# WM.net
KiCad netlist of a schematic drawn in EAGLE
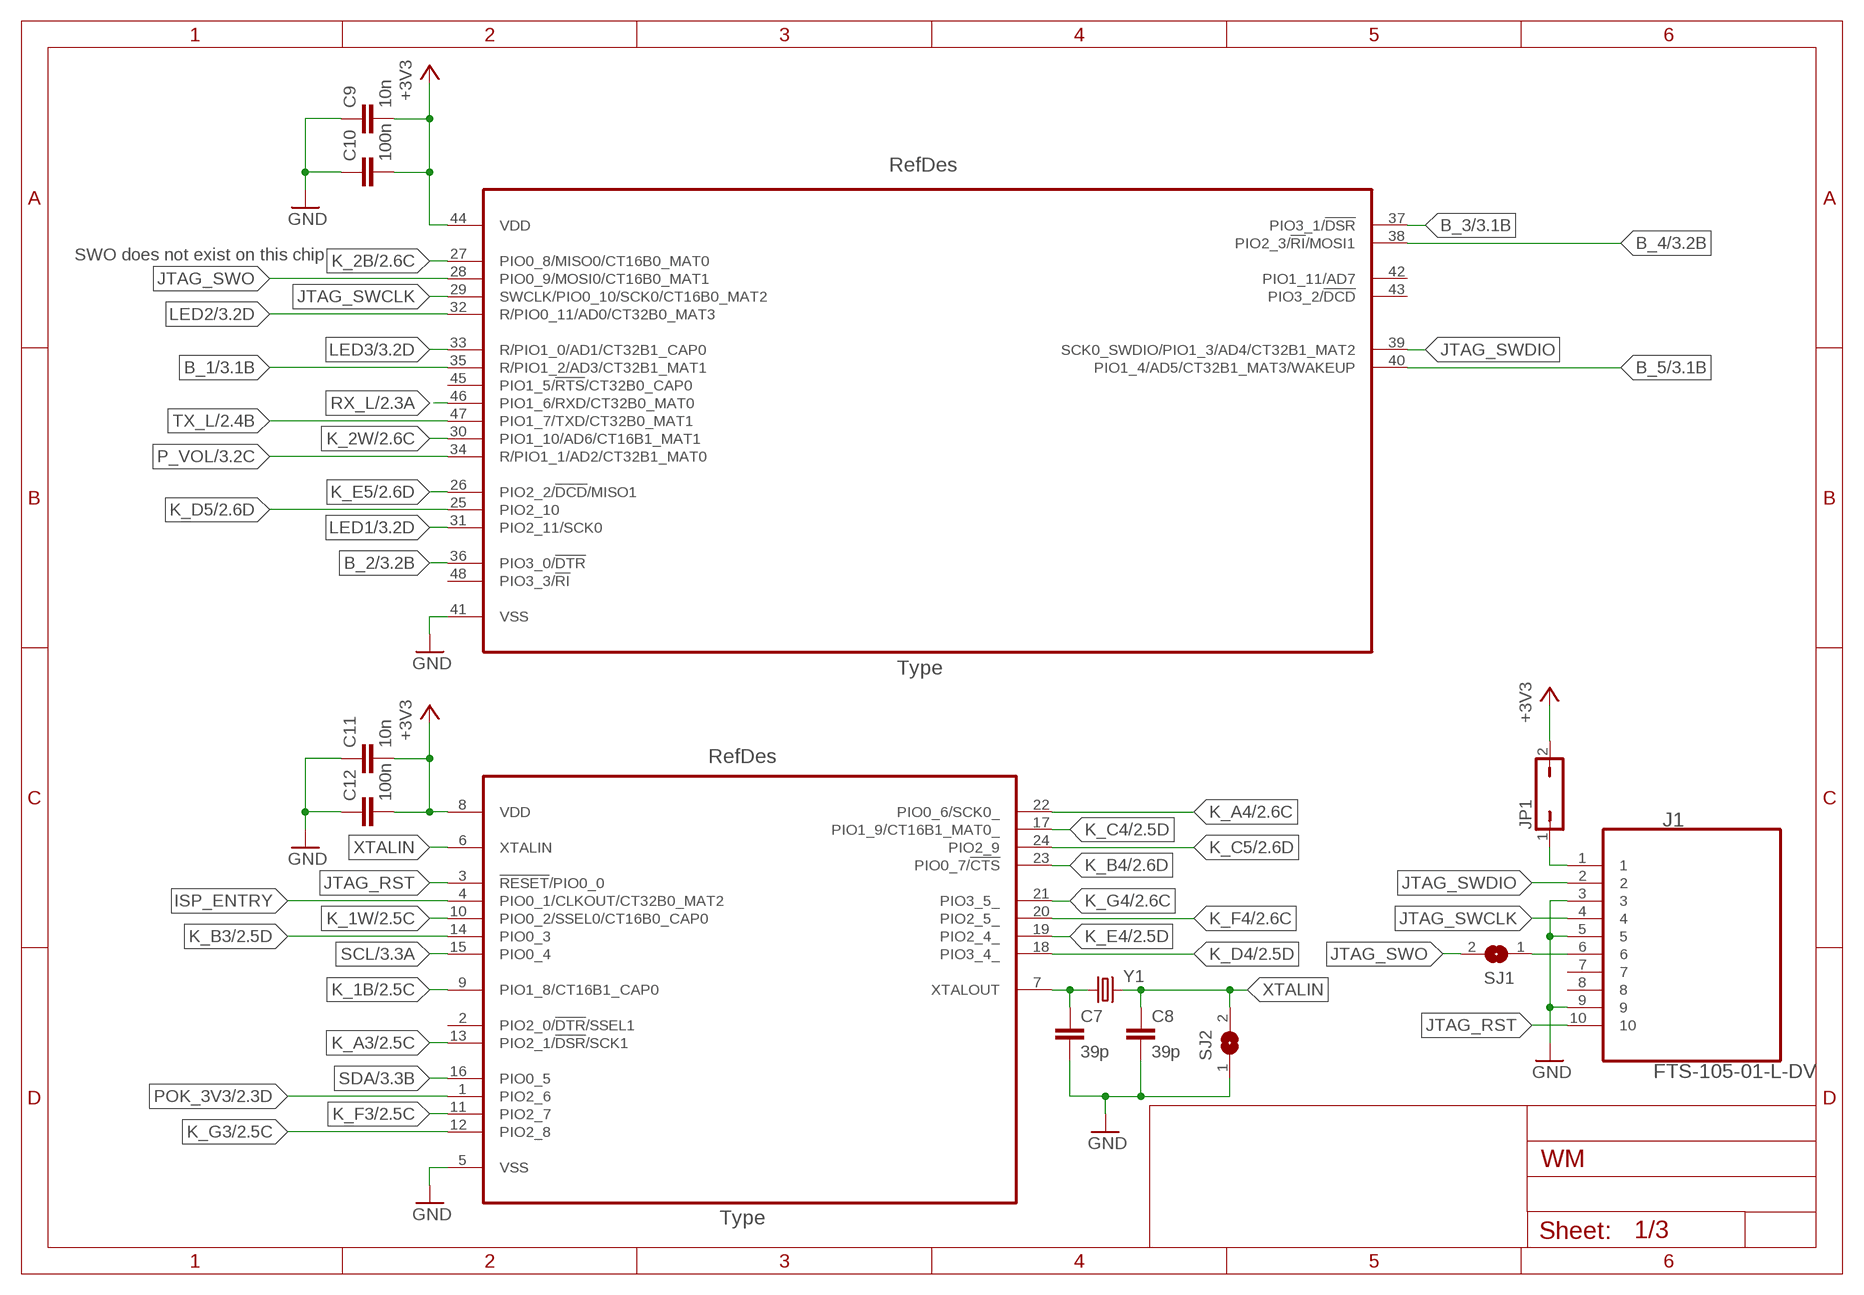
[diagram p0: schematic, sheet 1]
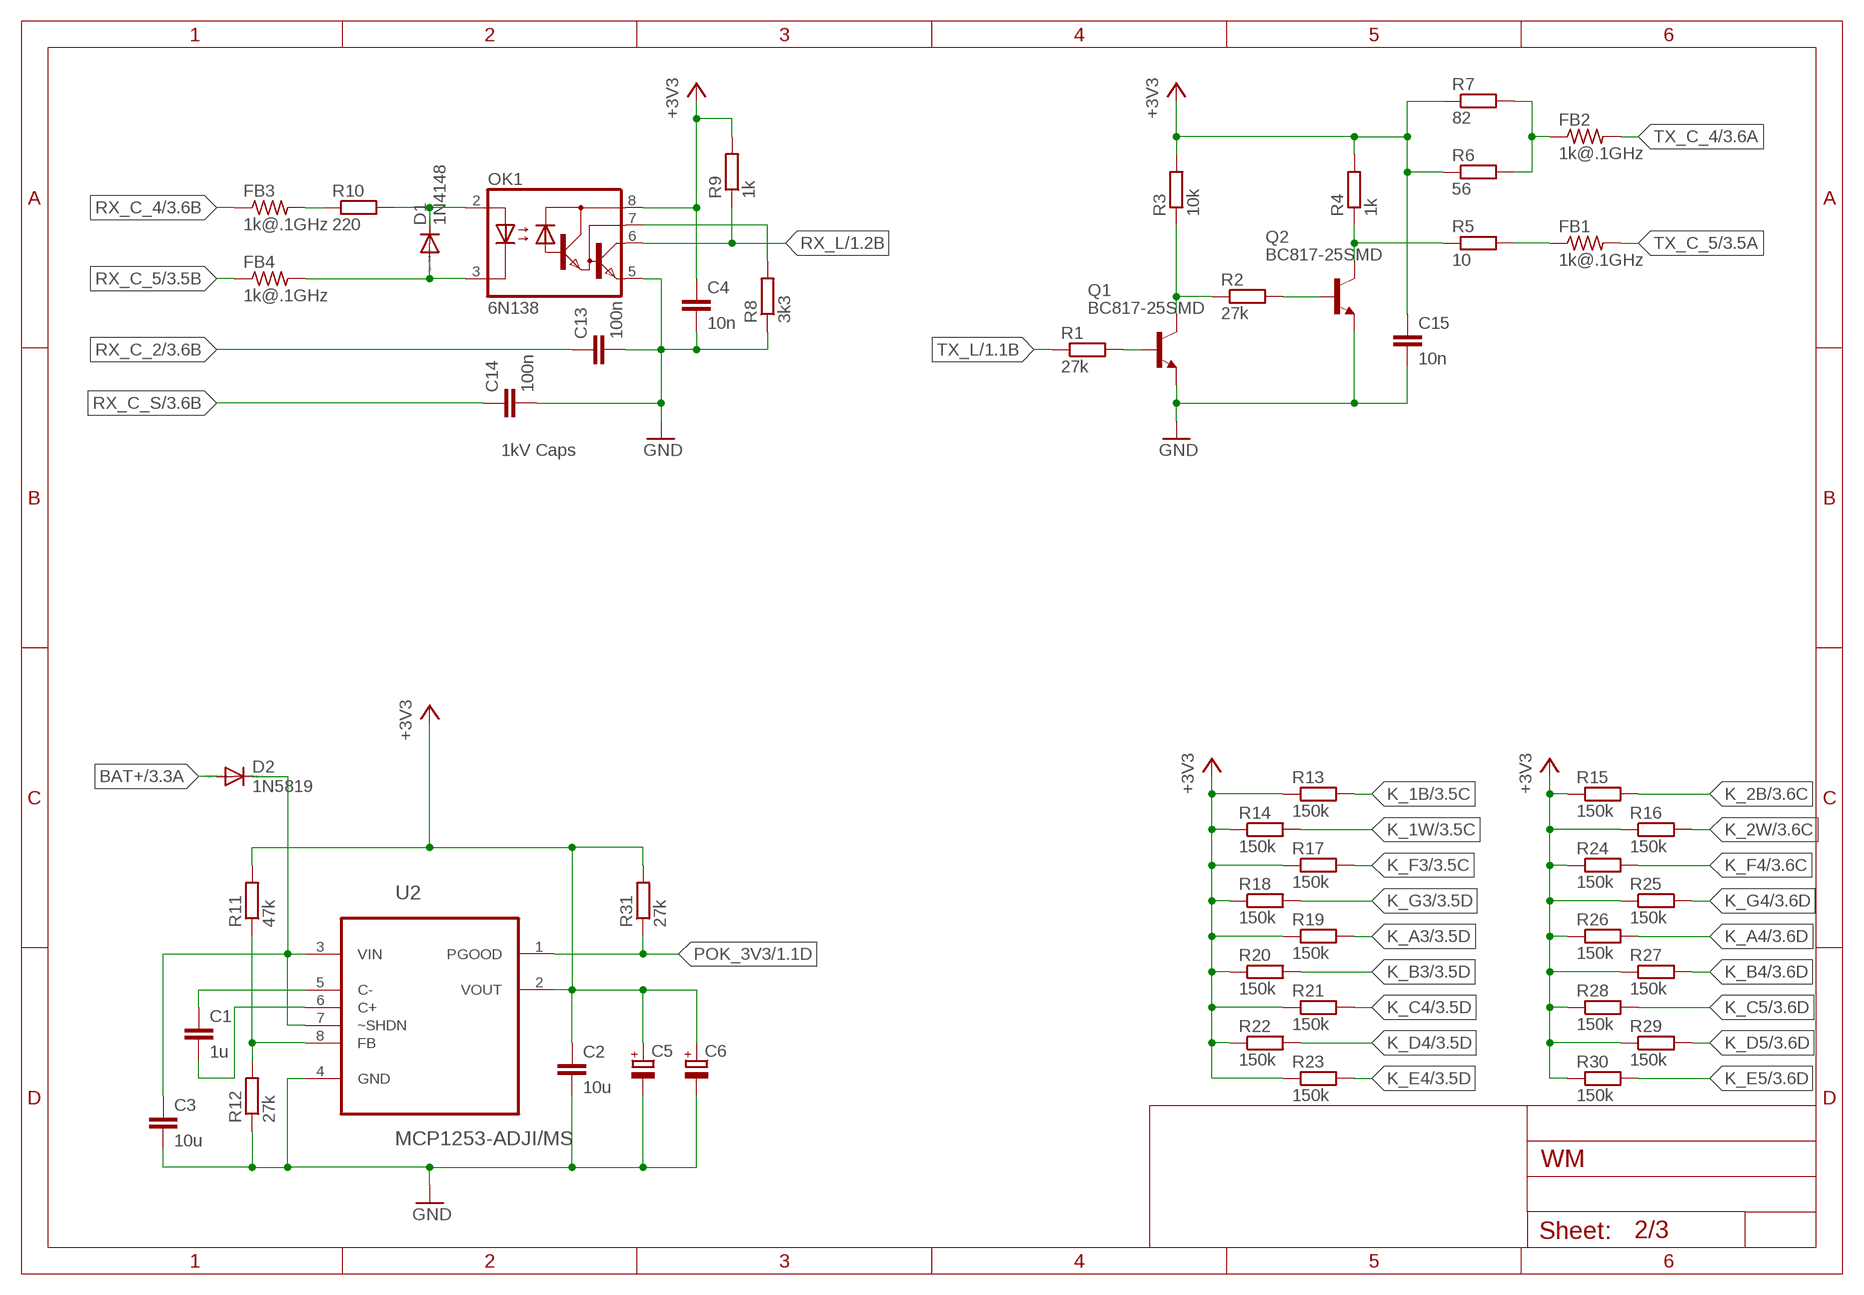
[diagram p1: schematic, sheet 2]
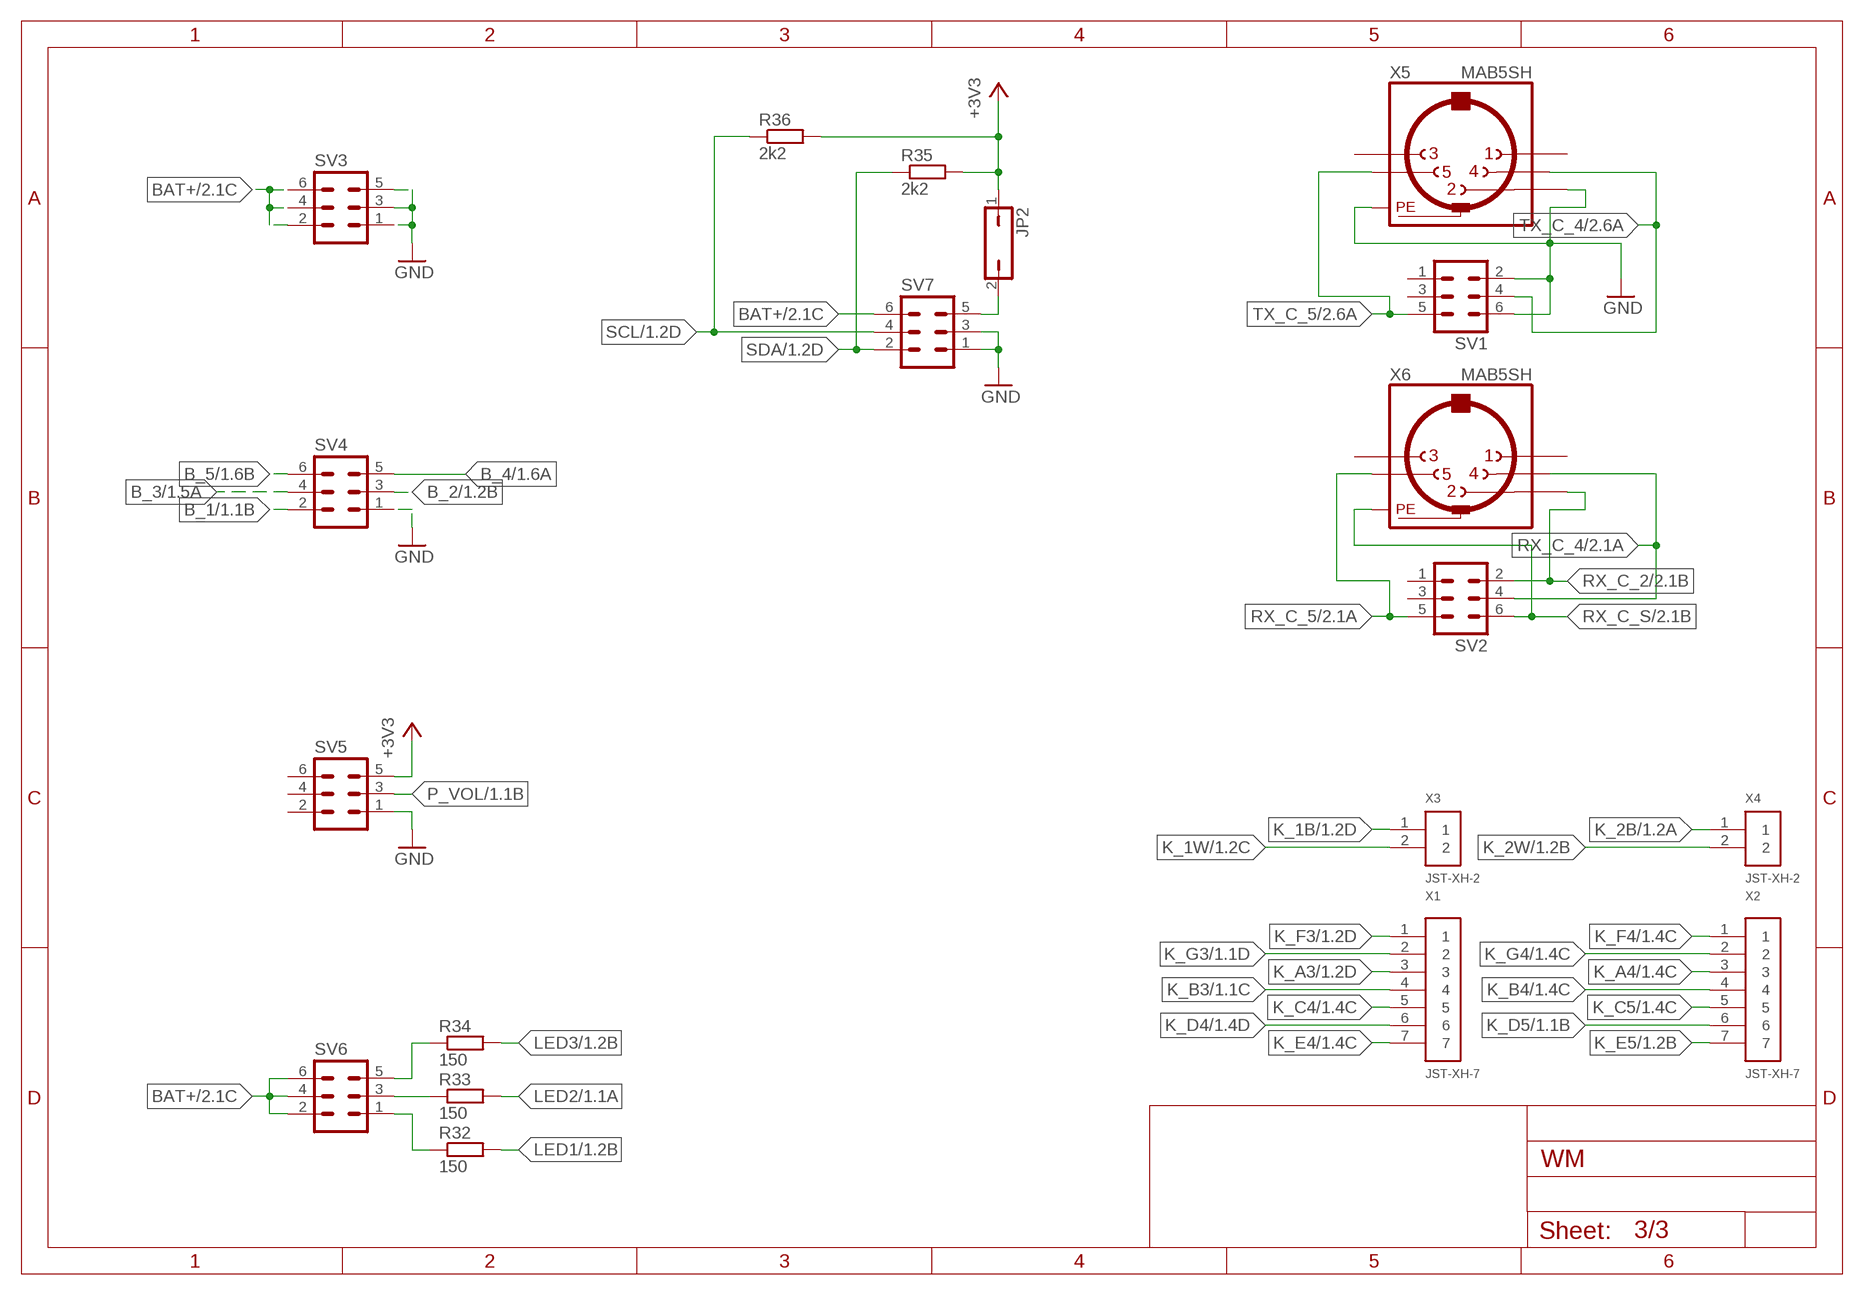
[diagram p2: schematic, sheet 3]

(export (version "E")
  (design (tool "Eeschema 10.0.6"))
  (components
    (comp (ref "C1")
      (value "1u")
      (footprint "eagle-import:C0805")
      (libsource (lib "eagle-import") (part "resistor_C-EUC0805"))
    )
    (comp (ref "C2")
      (value "10u")
      (footprint "eagle-import:C0805")
      (libsource (lib "eagle-import") (part "resistor_C-EUC0805"))
    )
    (comp (ref "C3")
      (value "10u")
      (footprint "eagle-import:C0805")
      (libsource (lib "eagle-import") (part "resistor_C-EUC0805"))
    )
    (comp (ref "C4")
      (value "10n")
      (footprint "eagle-import:C0805")
      (libsource (lib "eagle-import") (part "resistor_C-EUC0805"))
    )
    (comp (ref "C5")
      (value "CPOL-EUE2.5-6")
      (footprint "eagle-import:E2,5-6")
      (libsource (lib "eagle-import") (part "CPOL-EUE2.5-6"))
    )
    (comp (ref "C6")
      (value "CPOL-EUE2.5-6")
      (footprint "eagle-import:E2,5-6")
      (libsource (lib "eagle-import") (part "CPOL-EUE2.5-6"))
    )
    (comp (ref "C13")
      (value "100n")
      (footprint "eagle-import:C1210K")
      (libsource (lib "eagle-import") (part "resistor_C-EUC1210K"))
    )
    (comp (ref "C14")
      (value "100n")
      (footprint "eagle-import:C1210K")
      (libsource (lib "eagle-import") (part "resistor_C-EUC1210K"))
    )
    (comp (ref "C15")
      (value "10n")
      (footprint "eagle-import:C0805")
      (libsource (lib "eagle-import") (part "resistor_C-EUC0805"))
    )
    (comp (ref "D1")
      (value "1N4148")
      (footprint "eagle-import:SOD323-R")
      (libsource (lib "eagle-import") (part "DIODE-SOD323-R"))
    )
    (comp (ref "D2")
      (value "1N5819")
      (footprint "eagle-import:SOD123")
      (libsource (lib "eagle-import") (part "DIODE-SOD123"))
    )
    (comp (ref "FB1")
      (value "1k@.1GHz")
      (footprint "eagle-import:R0805")
      (libsource (lib "eagle-import") (part "R-US_R0805"))
    )
    (comp (ref "FB2")
      (value "1k@.1GHz")
      (footprint "eagle-import:R0805")
      (libsource (lib "eagle-import") (part "R-US_R0805"))
    )
    (comp (ref "FB3")
      (value "1k@.1GHz")
      (footprint "eagle-import:R0805")
      (libsource (lib "eagle-import") (part "R-US_R0805"))
    )
    (comp (ref "FB4")
      (value "1k@.1GHz")
      (footprint "eagle-import:R0805")
      (libsource (lib "eagle-import") (part "R-US_R0805"))
    )
    (comp (ref "OK1")
      (value "6N138")
      (footprint "eagle-import:DIL08")
      (fields (field (name "MF") "VISHAY/TELEFUNKEN"))
      (libsource (lib "eagle-import") (part "6N138"))
    )
    (comp (ref "Q1")
      (value "BC817-25SMD")
      (footprint "eagle-import:SOT23-BEC")
      (libsource (lib "eagle-import") (part "BC817SMD-25"))
    )
    (comp (ref "Q2")
      (value "BC817-25SMD")
      (footprint "eagle-import:SOT23-BEC")
      (libsource (lib "eagle-import") (part "BC817SMD-25"))
    )
    (comp (ref "R1")
      (value "27k")
      (footprint "eagle-import:R0805")
      (libsource (lib "eagle-import") (part "resistor_R-EU_R0805"))
    )
    (comp (ref "R2")
      (value "27k")
      (footprint "eagle-import:R0805")
      (libsource (lib "eagle-import") (part "resistor_R-EU_R0805"))
    )
    (comp (ref "R3")
      (value "10k")
      (footprint "eagle-import:R0805")
      (libsource (lib "eagle-import") (part "resistor_R-EU_R0805"))
    )
    (comp (ref "R4")
      (value "1k")
      (footprint "eagle-import:R0805")
      (libsource (lib "eagle-import") (part "resistor_R-EU_R0805"))
    )
    (comp (ref "R5")
      (value "10")
      (footprint "eagle-import:R0805")
      (libsource (lib "eagle-import") (part "resistor_R-EU_R0805"))
    )
    (comp (ref "R6")
      (value "56")
      (footprint "eagle-import:R0805")
      (libsource (lib "eagle-import") (part "resistor_R-EU_R0805"))
    )
    (comp (ref "R7")
      (value "82")
      (footprint "eagle-import:R0805")
      (libsource (lib "eagle-import") (part "resistor_R-EU_R0805"))
    )
    (comp (ref "R8")
      (value "3k3")
      (footprint "eagle-import:R0805")
      (libsource (lib "eagle-import") (part "resistor_R-EU_R0805"))
    )
    (comp (ref "R9")
      (value "1k")
      (footprint "eagle-import:R0805")
      (libsource (lib "eagle-import") (part "resistor_R-EU_R0805"))
    )
    (comp (ref "R10")
      (value "220")
      (footprint "eagle-import:R0805")
      (libsource (lib "eagle-import") (part "resistor_R-EU_R0805"))
    )
    (comp (ref "R11")
      (value "47k")
      (footprint "eagle-import:R0805")
      (libsource (lib "eagle-import") (part "R-EU_R0805"))
    )
    (comp (ref "R12")
      (value "27k")
      (footprint "eagle-import:R0805")
      (libsource (lib "eagle-import") (part "R-EU_R0805"))
    )
    (comp (ref "R13")
      (value "150k")
      (footprint "eagle-import:R0805")
      (libsource (lib "eagle-import") (part "R-EU_R0805"))
    )
    (comp (ref "R14")
      (value "150k")
      (footprint "eagle-import:R0805")
      (libsource (lib "eagle-import") (part "R-EU_R0805"))
    )
    (comp (ref "R15")
      (value "150k")
      (footprint "eagle-import:R0805")
      (libsource (lib "eagle-import") (part "R-EU_R0805"))
    )
    (comp (ref "R16")
      (value "150k")
      (footprint "eagle-import:R0805")
      (libsource (lib "eagle-import") (part "R-EU_R0805"))
    )
    (comp (ref "R17")
      (value "150k")
      (footprint "eagle-import:R0805")
      (libsource (lib "eagle-import") (part "R-EU_R0805"))
    )
    (comp (ref "R18")
      (value "150k")
      (footprint "eagle-import:R0805")
      (libsource (lib "eagle-import") (part "R-EU_R0805"))
    )
    (comp (ref "R19")
      (value "150k")
      (footprint "eagle-import:R0805")
      (libsource (lib "eagle-import") (part "R-EU_R0805"))
    )
    (comp (ref "R20")
      (value "150k")
      (footprint "eagle-import:R0805")
      (libsource (lib "eagle-import") (part "R-EU_R0805"))
    )
    (comp (ref "R21")
      (value "150k")
      (footprint "eagle-import:R0805")
      (libsource (lib "eagle-import") (part "R-EU_R0805"))
    )
    (comp (ref "R22")
      (value "150k")
      (footprint "eagle-import:R0805")
      (libsource (lib "eagle-import") (part "R-EU_R0805"))
    )
    (comp (ref "R23")
      (value "150k")
      (footprint "eagle-import:R0805")
      (libsource (lib "eagle-import") (part "R-EU_R0805"))
    )
    (comp (ref "R24")
      (value "150k")
      (footprint "eagle-import:R0805")
      (libsource (lib "eagle-import") (part "R-EU_R0805"))
    )
    (comp (ref "R25")
      (value "150k")
      (footprint "eagle-import:R0805")
      (libsource (lib "eagle-import") (part "R-EU_R0805"))
    )
    (comp (ref "R26")
      (value "150k")
      (footprint "eagle-import:R0805")
      (libsource (lib "eagle-import") (part "R-EU_R0805"))
    )
    (comp (ref "R27")
      (value "150k")
      (footprint "eagle-import:R0805")
      (libsource (lib "eagle-import") (part "R-EU_R0805"))
    )
    (comp (ref "R28")
      (value "150k")
      (footprint "eagle-import:R0805")
      (libsource (lib "eagle-import") (part "R-EU_R0805"))
    )
    (comp (ref "R29")
      (value "150k")
      (footprint "eagle-import:R0805")
      (libsource (lib "eagle-import") (part "R-EU_R0805"))
    )
    (comp (ref "R30")
      (value "150k")
      (footprint "eagle-import:R0805")
      (libsource (lib "eagle-import") (part "R-EU_R0805"))
    )
    (comp (ref "R31")
      (value "27k")
      (footprint "eagle-import:R0805")
      (libsource (lib "eagle-import") (part "resistor_R-EU_R0805"))
    )
    (comp (ref "U2")
      (value "MCP1253-ADJI/MS")
      (footprint "eagle-import:SOP65P490X118-8N")
      (libsource (lib "eagle-import") (part "MCP1253-ADJI/MS"))
    )
    (comp (ref "JP2")
      (value "JP1Q")
      (footprint "eagle-import:JP1")
      (libsource (lib "eagle-import") (part "JP1Q"))
    )
    (comp (ref "R32")
      (value "150")
      (footprint "eagle-import:R0805")
      (libsource (lib "eagle-import") (part "resistor_R-EU_R0805"))
    )
    (comp (ref "R33")
      (value "150")
      (footprint "eagle-import:R0805")
      (libsource (lib "eagle-import") (part "resistor_R-EU_R0805"))
    )
    (comp (ref "R34")
      (value "150")
      (footprint "eagle-import:R0805")
      (libsource (lib "eagle-import") (part "resistor_R-EU_R0805"))
    )
    (comp (ref "R35")
      (value "2k2")
      (footprint "eagle-import:R0805")
      (libsource (lib "eagle-import") (part "resistor_R-EU_R0805"))
    )
    (comp (ref "R36")
      (value "2k2")
      (footprint "eagle-import:R0805")
      (libsource (lib "eagle-import") (part "resistor_R-EU_R0805"))
    )
    (comp (ref "SV1")
      (value "ML6")
      (footprint "eagle-import:ML6")
      (libsource (lib "eagle-import") (part "ML6"))
    )
    (comp (ref "SV2")
      (value "ML6")
      (footprint "eagle-import:ML6")
      (libsource (lib "eagle-import") (part "ML6"))
    )
    (comp (ref "SV3")
      (value "ML6")
      (footprint "eagle-import:ML6")
      (libsource (lib "eagle-import") (part "ML6"))
    )
    (comp (ref "SV4")
      (value "ML6")
      (footprint "eagle-import:ML6")
      (libsource (lib "eagle-import") (part "ML6"))
    )
    (comp (ref "SV5")
      (value "ML6")
      (footprint "eagle-import:ML6")
      (libsource (lib "eagle-import") (part "ML6"))
    )
    (comp (ref "SV6")
      (value "ML6")
      (footprint "eagle-import:ML6")
      (libsource (lib "eagle-import") (part "ML6"))
    )
    (comp (ref "SV7")
      (value "ML6")
      (footprint "eagle-import:ML6")
      (libsource (lib "eagle-import") (part "ML6"))
    )
    (comp (ref "X1")
      (value "JST-XH-7")
      (footprint "eagle-import:JST-XH-7")
      (fields (field (name "MF") "MOLEX") (field (name "MPN") "22-23-2071"))
      (libsource (lib "eagle-import") (part "JST-XH-7"))
    )
    (comp (ref "X2")
      (value "JST-XH-7")
      (footprint "eagle-import:JST-XH-7")
      (fields (field (name "MF") "MOLEX") (field (name "MPN") "22-23-2071"))
      (libsource (lib "eagle-import") (part "JST-XH-7"))
    )
    (comp (ref "X3")
      (value "JST-XH-2")
      (footprint "eagle-import:JST-XH-2")
      (libsource (lib "eagle-import") (part "JST-XH-2"))
    )
    (comp (ref "X4")
      (value "JST-XH-2")
      (footprint "eagle-import:JST-XH-2")
      (libsource (lib "eagle-import") (part "JST-XH-2"))
    )
    (comp (ref "X5")
      (value "MAB5SH")
      (footprint "eagle-import:MAB5SH")
      (libsource (lib "eagle-import") (part "MAB5SH"))
    )
    (comp (ref "X6")
      (value "MAB5SH")
      (footprint "eagle-import:MAB5SH")
      (libsource (lib "eagle-import") (part "MAB5SH"))
    )
    (comp (ref "C7")
      (value "39p")
      (footprint "eagle-import:C0805")
      (libsource (lib "eagle-import") (part "resistor_C-EUC0805"))
    )
    (comp (ref "C8")
      (value "39p")
      (footprint "eagle-import:C0805")
      (libsource (lib "eagle-import") (part "resistor_C-EUC0805"))
    )
    (comp (ref "C9")
      (value "10n")
      (footprint "eagle-import:C0805")
      (libsource (lib "eagle-import") (part "C-EUC0805"))
    )
    (comp (ref "C10")
      (value "100n")
      (footprint "eagle-import:C0805")
      (libsource (lib "eagle-import") (part "C-EUC0805"))
    )
    (comp (ref "C11")
      (value "10n")
      (footprint "eagle-import:C0805")
      (libsource (lib "eagle-import") (part "C-EUC0805"))
    )
    (comp (ref "C12")
      (value "100n")
      (footprint "eagle-import:C0805")
      (libsource (lib "eagle-import") (part "C-EUC0805"))
    )
    (comp (ref "J1")
      (value "FTS-105-01-L-DV")
      (footprint "eagle-import:SAMTEC_FTS-105-01-L-DV")
      (libsource (lib "eagle-import") (part "FTS-105-01-L-DV"))
    )
    (comp (ref "JP1")
      (value "JP1Q")
      (footprint "eagle-import:JP1")
      (libsource (lib "eagle-import") (part "JP1Q"))
    )
    (comp (ref "SJ1") (value "SJ") (footprint "eagle-import:SJ") (libsource (lib "eagle-import") (part "SJ")))
    (comp (ref "SJ2") (value "SJ") (footprint "eagle-import:SJ") (libsource (lib "eagle-import") (part "SJ")))
    (comp (ref "U1")
      (value "LPC1113FBD48/302,1")
      (footprint "eagle-import:QFP50P900X900X160-48N")
      (libsource (lib "eagle-import") (part "LPC1113FBD48/302,1"))
    )
    (comp (ref "Y1")
      (value "CRYSTALHC49UP")
      (footprint "eagle-import:HC49UP")
      (libsource (lib "eagle-import") (part "CRYSTALHC49UP"))
    )
  )
  (nets
    (net (code "1") (name "+3V3") (class "Default")
      (node (ref "C10") (pin "2") (pinfunction "2_2") (pintype "passive"))
      (node (ref "C11") (pin "2") (pinfunction "2_2") (pintype "passive"))
      (node (ref "C12") (pin "2") (pinfunction "2_2") (pintype "passive"))
      (node (ref "C15") (pin "1") (pinfunction "1_1") (pintype "passive"))
      (node (ref "C2") (pin "1") (pinfunction "1_1") (pintype "passive"))
      (node (ref "C4") (pin "1") (pinfunction "1_1") (pintype "passive"))
      (node (ref "C5") (pin "+") (pinfunction "+_+") (pintype "passive"))
      (node (ref "C6") (pin "+") (pinfunction "+_+") (pintype "passive"))
      (node (ref "C9") (pin "2") (pinfunction "2_2") (pintype "passive"))
      (node (ref "JP1") (pin "2") (pinfunction "2_2") (pintype "passive"))
      (node (ref "JP2") (pin "1") (pinfunction "1_1") (pintype "passive"))
      (node (ref "OK1") (pin "8") (pinfunction "VCC_8") (pintype "passive"))
      (node (ref "R11") (pin "2") (pinfunction "2_2") (pintype "passive"))
      (node (ref "R13") (pin "1") (pinfunction "1_1") (pintype "passive"))
      (node (ref "R14") (pin "1") (pinfunction "1_1") (pintype "passive"))
      (node (ref "R15") (pin "1") (pinfunction "1_1") (pintype "passive"))
      (node (ref "R16") (pin "1") (pinfunction "1_1") (pintype "passive"))
      (node (ref "R17") (pin "1") (pinfunction "1_1") (pintype "passive"))
      (node (ref "R18") (pin "1") (pinfunction "1_1") (pintype "passive"))
      (node (ref "R19") (pin "1") (pinfunction "1_1") (pintype "passive"))
      (node (ref "R20") (pin "1") (pinfunction "1_1") (pintype "passive"))
      (node (ref "R21") (pin "1") (pinfunction "1_1") (pintype "passive"))
      (node (ref "R22") (pin "1") (pinfunction "1_1") (pintype "passive"))
      (node (ref "R23") (pin "1") (pinfunction "1_1") (pintype "passive"))
      (node (ref "R24") (pin "1") (pinfunction "1_1") (pintype "passive"))
      (node (ref "R25") (pin "1") (pinfunction "1_1") (pintype "passive"))
      (node (ref "R26") (pin "1") (pinfunction "1_1") (pintype "passive"))
      (node (ref "R27") (pin "1") (pinfunction "1_1") (pintype "passive"))
      (node (ref "R28") (pin "1") (pinfunction "1_1") (pintype "passive"))
      (node (ref "R29") (pin "1") (pinfunction "1_1") (pintype "passive"))
      (node (ref "R3") (pin "2") (pinfunction "2_2") (pintype "passive"))
      (node (ref "R30") (pin "1") (pinfunction "1_1") (pintype "passive"))
      (node (ref "R31") (pin "2") (pinfunction "2_2") (pintype "passive"))
      (node (ref "R35") (pin "2") (pinfunction "2_2") (pintype "passive"))
      (node (ref "R36") (pin "2") (pinfunction "2_2") (pintype "passive"))
      (node (ref "R4") (pin "2") (pinfunction "2_2") (pintype "passive"))
      (node (ref "R6") (pin "1") (pinfunction "1_1") (pintype "passive"))
      (node (ref "R7") (pin "1") (pinfunction "1_1") (pintype "passive"))
      (node (ref "R9") (pin "2") (pinfunction "2_2") (pintype "passive"))
      (node (ref "SV5") (pin "5") (pinfunction "5_5") (pintype "passive"))
      (node (ref "U1") (pin "44") (pinfunction "VDD_44") (pintype "power_in"))
      (node (ref "U1") (pin "8") (pinfunction "VDD_8") (pintype "power_in"))
      (node (ref "U2") (pin "2") (pinfunction "VOUT_2") (pintype "output"))
    )
    (net (code "2") (name "BAT+") (class "Default")
      (node (ref "D2") (pin "A") (pinfunction "A_A") (pintype "passive"))
      (node (ref "SV3") (pin "2") (pinfunction "2_2") (pintype "passive"))
      (node (ref "SV3") (pin "4") (pinfunction "4_4") (pintype "passive"))
      (node (ref "SV3") (pin "6") (pinfunction "6_6") (pintype "passive"))
      (node (ref "SV6") (pin "2") (pinfunction "2_2") (pintype "passive"))
      (node (ref "SV6") (pin "4") (pinfunction "4_4") (pintype "passive"))
      (node (ref "SV6") (pin "6") (pinfunction "6_6") (pintype "passive"))
      (node (ref "SV7") (pin "6") (pinfunction "6_6") (pintype "passive"))
    )
    (net (code "3") (name "B_1") (class "Default")
      (node (ref "SV4") (pin "2") (pinfunction "2_2") (pintype "passive"))
      (node (ref "U1") (pin "35") (pinfunction "R/PIO1_2/AD3/CT32B1_MAT1_35") (pintype "bidirectional"))
    )
    (net (code "4") (name "B_2") (class "Default")
      (node (ref "SV4") (pin "3") (pinfunction "3_3") (pintype "passive"))
      (node (ref "U1") (pin "36") (pinfunction "PIO3_0/~{DTR}_36") (pintype "bidirectional"))
    )
    (net (code "5") (name "B_3") (class "Default")
      (node (ref "SV4") (pin "4") (pinfunction "4_4") (pintype "passive"))
      (node (ref "U1") (pin "37") (pinfunction "PIO3_1/~{DSR}_37") (pintype "bidirectional"))
    )
    (net (code "6") (name "B_4") (class "Default")
      (node (ref "SV4") (pin "5") (pinfunction "5_5") (pintype "passive"))
      (node (ref "U1") (pin "38") (pinfunction "PIO2_3/~{RI}/MOSI1_38") (pintype "bidirectional"))
    )
    (net (code "7") (name "B_5") (class "Default")
      (node (ref "SV4") (pin "6") (pinfunction "6_6") (pintype "passive"))
      (node (ref "U1") (pin "40") (pinfunction "PIO1_4/AD5/CT32B1_MAT3/WAKEUP_40") (pintype "bidirectional"))
    )
    (net (code "8") (name "GND") (class "Default")
      (node (ref "C10") (pin "1") (pinfunction "1_1") (pintype "passive"))
      (node (ref "C11") (pin "1") (pinfunction "1_1") (pintype "passive"))
      (node (ref "C12") (pin "1") (pinfunction "1_1") (pintype "passive"))
      (node (ref "C13") (pin "2") (pinfunction "2_2") (pintype "passive"))
      (node (ref "C14") (pin "2") (pinfunction "2_2") (pintype "passive"))
      (node (ref "C15") (pin "2") (pinfunction "2_2") (pintype "passive"))
      (node (ref "C2") (pin "2") (pinfunction "2_2") (pintype "passive"))
      (node (ref "C3") (pin "2") (pinfunction "2_2") (pintype "passive"))
      (node (ref "C4") (pin "2") (pinfunction "2_2") (pintype "passive"))
      (node (ref "C5") (pin "-") (pinfunction "-_-") (pintype "passive"))
      (node (ref "C6") (pin "-") (pinfunction "-_-") (pintype "passive"))
      (node (ref "C7") (pin "2") (pinfunction "2_2") (pintype "passive"))
      (node (ref "C8") (pin "2") (pinfunction "2_2") (pintype "passive"))
      (node (ref "C9") (pin "1") (pinfunction "1_1") (pintype "passive"))
      (node (ref "J1") (pin "3") (pinfunction "3_3") (pintype "passive"))
      (node (ref "J1") (pin "5") (pinfunction "5_5") (pintype "passive"))
      (node (ref "J1") (pin "9") (pinfunction "9_9") (pintype "passive"))
      (node (ref "OK1") (pin "5") (pinfunction "GND_5") (pintype "passive"))
      (node (ref "Q1") (pin "E") (pinfunction "E_E") (pintype "passive"))
      (node (ref "Q2") (pin "E") (pinfunction "E_E") (pintype "passive"))
      (node (ref "R12") (pin "1") (pinfunction "1_1") (pintype "passive"))
      (node (ref "R8") (pin "1") (pinfunction "1_1") (pintype "passive"))
      (node (ref "SJ2") (pin "1") (pinfunction "1_1") (pintype "passive"))
      (node (ref "SV1") (pin "2") (pinfunction "2_2") (pintype "passive"))
      (node (ref "SV1") (pin "6") (pinfunction "6_6") (pintype "passive"))
      (node (ref "SV3") (pin "1") (pinfunction "1_1") (pintype "passive"))
      (node (ref "SV3") (pin "3") (pinfunction "3_3") (pintype "passive"))
      (node (ref "SV3") (pin "5") (pinfunction "5_5") (pintype "passive"))
      (node (ref "SV4") (pin "1") (pinfunction "1_1") (pintype "passive"))
      (node (ref "SV5") (pin "1") (pinfunction "1_1") (pintype "passive"))
      (node (ref "SV7") (pin "1") (pinfunction "1_1") (pintype "passive"))
      (node (ref "SV7") (pin "3") (pinfunction "3_3") (pintype "passive"))
      (node (ref "U1") (pin "41") (pinfunction "VSS_41") (pintype "passive"))
      (node (ref "U1") (pin "5") (pinfunction "VSS_5") (pintype "passive"))
      (node (ref "U2") (pin "4") (pinfunction "GND_4") (pintype "passive"))
      (node (ref "X5") (pin "2") (pinfunction "2_2") (pintype "passive"))
      (node (ref "X5") (pin "PE") (pinfunction "PE_PE") (pintype "power_in"))
      (node (ref "X5") (pin "PE@") (pinfunction "PE_PE@") (pintype "power_in"))
    )
    (net (code "9") (name "ISP_ENTRY") (class "Default")
      (node (ref "U1") (pin "4") (pinfunction "PIO0_1/CLKOUT/CT32B0_MAT2_4") (pintype "bidirectional"))
    )
    (net (code "10") (name "JTAG_RST") (class "Default")
      (node (ref "J1") (pin "10") (pinfunction "10_10") (pintype "passive"))
      (node (ref "U1") (pin "3") (pinfunction "~{RESET}/PIO0_0_3") (pintype "input"))
    )
    (net (code "11") (name "JTAG_SWCLK") (class "Default")
      (node (ref "J1") (pin "4") (pinfunction "4_4") (pintype "passive"))
      (node (ref "U1") (pin "29") (pinfunction "SWCLK/PIO0_10/SCK0/CT16B0_MAT2_29") (pintype "bidirectional"))
    )
    (net (code "12") (name "JTAG_SWDIO") (class "Default")
      (node (ref "J1") (pin "2") (pinfunction "2_2") (pintype "passive"))
      (node (ref "U1") (pin "39") (pinfunction "SCK0_SWDIO/PIO1_3/AD4/CT32B1_MAT2_39") (pintype "bidirectional"))
    )
    (net (code "13") (name "JTAG_SWO") (class "Default")
      (node (ref "SJ1") (pin "2") (pinfunction "2_2") (pintype "passive"))
      (node (ref "U1") (pin "28") (pinfunction "PIO0_9/MOSI0/CT16B0_MAT1_28") (pintype "bidirectional"))
    )
    (net (code "14") (name "K_1B") (class "Default")
      (node (ref "R13") (pin "2") (pinfunction "2_2") (pintype "passive"))
      (node (ref "U1") (pin "9") (pinfunction "PIO1_8/CT16B1_CAP0_9") (pintype "bidirectional"))
      (node (ref "X3") (pin "1") (pinfunction "1_1") (pintype "bidirectional"))
    )
    (net (code "15") (name "K_1W") (class "Default")
      (node (ref "R14") (pin "2") (pinfunction "2_2") (pintype "passive"))
      (node (ref "U1") (pin "10") (pinfunction "PIO0_2/SSEL0/CT16B0_CAP0_10") (pintype "bidirectional"))
      (node (ref "X3") (pin "2") (pinfunction "2_2") (pintype "bidirectional"))
    )
    (net (code "16") (name "K_2B") (class "Default")
      (node (ref "R15") (pin "2") (pinfunction "2_2") (pintype "passive"))
      (node (ref "U1") (pin "27") (pinfunction "PIO0_8/MISO0/CT16B0_MAT0_27") (pintype "bidirectional"))
      (node (ref "X4") (pin "1") (pinfunction "1_1") (pintype "bidirectional"))
    )
    (net (code "17") (name "K_2W") (class "Default")
      (node (ref "R16") (pin "2") (pinfunction "2_2") (pintype "passive"))
      (node (ref "U1") (pin "30") (pinfunction "PIO1_10/AD6/CT16B1_MAT1_30") (pintype "bidirectional"))
      (node (ref "X4") (pin "2") (pinfunction "2_2") (pintype "bidirectional"))
    )
    (net (code "18") (name "K_A3") (class "Default")
      (node (ref "R19") (pin "2") (pinfunction "2_2") (pintype "passive"))
      (node (ref "U1") (pin "13") (pinfunction "PIO2_1/~{DSR}/SCK1_13") (pintype "bidirectional"))
      (node (ref "X1") (pin "3") (pinfunction "3_3") (pintype "bidirectional"))
    )
    (net (code "19") (name "K_A4") (class "Default")
      (node (ref "R26") (pin "2") (pinfunction "2_2") (pintype "passive"))
      (node (ref "U1") (pin "22") (pinfunction "PIO0_6/SCK0__22") (pintype "bidirectional"))
      (node (ref "X2") (pin "3") (pinfunction "3_3") (pintype "bidirectional"))
    )
    (net (code "20") (name "K_B3") (class "Default")
      (node (ref "R20") (pin "2") (pinfunction "2_2") (pintype "passive"))
      (node (ref "U1") (pin "14") (pinfunction "PIO0_3_14") (pintype "bidirectional"))
      (node (ref "X1") (pin "4") (pinfunction "4_4") (pintype "bidirectional"))
    )
    (net (code "21") (name "K_B4") (class "Default")
      (node (ref "R27") (pin "2") (pinfunction "2_2") (pintype "passive"))
      (node (ref "U1") (pin "23") (pinfunction "PIO0_7/~{CTS}_23") (pintype "bidirectional"))
      (node (ref "X2") (pin "4") (pinfunction "4_4") (pintype "bidirectional"))
    )
    (net (code "22") (name "K_C4") (class "Default")
      (node (ref "R21") (pin "2") (pinfunction "2_2") (pintype "passive"))
      (node (ref "U1") (pin "17") (pinfunction "PIO1_9/CT16B1_MAT0__17") (pintype "bidirectional"))
      (node (ref "X1") (pin "5") (pinfunction "5_5") (pintype "bidirectional"))
    )
    (net (code "23") (name "K_C5") (class "Default")
      (node (ref "R28") (pin "2") (pinfunction "2_2") (pintype "passive"))
      (node (ref "U1") (pin "24") (pinfunction "PIO2_9_24") (pintype "bidirectional"))
      (node (ref "X2") (pin "5") (pinfunction "5_5") (pintype "bidirectional"))
    )
    (net (code "24") (name "K_D4") (class "Default")
      (node (ref "R22") (pin "2") (pinfunction "2_2") (pintype "passive"))
      (node (ref "U1") (pin "18") (pinfunction "PIO3_4__18") (pintype "bidirectional"))
      (node (ref "X1") (pin "6") (pinfunction "6_6") (pintype "bidirectional"))
    )
    (net (code "25") (name "K_D5") (class "Default")
      (node (ref "R29") (pin "2") (pinfunction "2_2") (pintype "passive"))
      (node (ref "U1") (pin "25") (pinfunction "PIO2_10_25") (pintype "bidirectional"))
      (node (ref "X2") (pin "6") (pinfunction "6_6") (pintype "bidirectional"))
    )
    (net (code "26") (name "K_E4") (class "Default")
      (node (ref "R23") (pin "2") (pinfunction "2_2") (pintype "passive"))
      (node (ref "U1") (pin "19") (pinfunction "PIO2_4__19") (pintype "bidirectional"))
      (node (ref "X1") (pin "7") (pinfunction "7_7") (pintype "bidirectional"))
    )
    (net (code "27") (name "K_E5") (class "Default")
      (node (ref "R30") (pin "2") (pinfunction "2_2") (pintype "passive"))
      (node (ref "U1") (pin "26") (pinfunction "PIO2_2/~{DCD}/MISO1_26") (pintype "bidirectional"))
      (node (ref "X2") (pin "7") (pinfunction "7_7") (pintype "bidirectional"))
    )
    (net (code "28") (name "K_F3") (class "Default")
      (node (ref "R17") (pin "2") (pinfunction "2_2") (pintype "passive"))
      (node (ref "U1") (pin "11") (pinfunction "PIO2_7_11") (pintype "bidirectional"))
      (node (ref "X1") (pin "1") (pinfunction "1_1") (pintype "bidirectional"))
    )
    (net (code "29") (name "K_F4") (class "Default")
      (node (ref "R24") (pin "2") (pinfunction "2_2") (pintype "passive"))
      (node (ref "U1") (pin "20") (pinfunction "PIO2_5__20") (pintype "bidirectional"))
      (node (ref "X2") (pin "1") (pinfunction "1_1") (pintype "bidirectional"))
    )
    (net (code "30") (name "K_G3") (class "Default")
      (node (ref "R18") (pin "2") (pinfunction "2_2") (pintype "passive"))
      (node (ref "U1") (pin "12") (pinfunction "PIO2_8_12") (pintype "bidirectional"))
      (node (ref "X1") (pin "2") (pinfunction "2_2") (pintype "bidirectional"))
    )
    (net (code "31") (name "K_G4") (class "Default")
      (node (ref "R25") (pin "2") (pinfunction "2_2") (pintype "passive"))
      (node (ref "U1") (pin "21") (pinfunction "PIO3_5__21") (pintype "bidirectional"))
      (node (ref "X2") (pin "2") (pinfunction "2_2") (pintype "bidirectional"))
    )
    (net (code "32") (name "LED1") (class "Default")
      (node (ref "R32") (pin "2") (pinfunction "2_2") (pintype "passive"))
      (node (ref "U1") (pin "31") (pinfunction "PIO2_11/SCK0_31") (pintype "bidirectional"))
    )
    (net (code "33") (name "LED2") (class "Default")
      (node (ref "R33") (pin "2") (pinfunction "2_2") (pintype "passive"))
      (node (ref "U1") (pin "32") (pinfunction "R/PIO0_11/AD0/CT32B0_MAT3_32") (pintype "bidirectional"))
    )
    (net (code "34") (name "LED3") (class "Default")
      (node (ref "R34") (pin "2") (pinfunction "2_2") (pintype "passive"))
      (node (ref "U1") (pin "33") (pinfunction "R/PIO1_0/AD1/CT32B1_CAP0_33") (pintype "bidirectional"))
    )
    (net (code "35") (name "Net-(FB1-Pad1)") (class "Default")
      (node (ref "FB1") (pin "1") (pinfunction "1_1") (pintype "passive"))
      (node (ref "R5") (pin "2") (pinfunction "2_2") (pintype "passive"))
    )
    (net (code "36") (name "Net-(FB2-Pad1)") (class "Default")
      (node (ref "FB2") (pin "1") (pinfunction "1_1") (pintype "passive"))
      (node (ref "R6") (pin "2") (pinfunction "2_2") (pintype "passive"))
      (node (ref "R7") (pin "2") (pinfunction "2_2") (pintype "passive"))
    )
    (net (code "37") (name "Net-(FB3-Pad2)") (class "Default")
      (node (ref "FB3") (pin "2") (pinfunction "2_2") (pintype "passive"))
      (node (ref "R10") (pin "1") (pinfunction "1_1") (pintype "passive"))
    )
    (net (code "38") (name "Net-(J1-Pad1)") (class "Default")
      (node (ref "J1") (pin "1") (pinfunction "1_1") (pintype "passive"))
      (node (ref "JP1") (pin "1") (pinfunction "1_1") (pintype "passive"))
    )
    (net (code "39") (name "Net-(J1-Pad6)") (class "Default")
      (node (ref "J1") (pin "6") (pinfunction "6_6") (pintype "passive"))
      (node (ref "SJ1") (pin "1") (pinfunction "1_1") (pintype "passive"))
    )
    (net (code "40") (name "Net-(JP2-Pad2)") (class "Default")
      (node (ref "JP2") (pin "2") (pinfunction "2_2") (pintype "passive"))
      (node (ref "SV7") (pin "5") (pinfunction "5_5") (pintype "passive"))
    )
    (net (code "41") (name "Net-(OK1-A)") (class "Default")
      (node (ref "D1") (pin "C") (pinfunction "C_C") (pintype "passive"))
      (node (ref "OK1") (pin "2") (pinfunction "A_2") (pintype "passive"))
      (node (ref "R10") (pin "2") (pinfunction "2_2") (pintype "passive"))
    )
    (net (code "42") (name "Net-(OK1-C)") (class "Default")
      (node (ref "D1") (pin "A") (pinfunction "A_A") (pintype "passive"))
      (node (ref "FB4") (pin "2") (pinfunction "2_2") (pintype "passive"))
      (node (ref "OK1") (pin "3") (pinfunction "C_3") (pintype "passive"))
    )
    (net (code "43") (name "Net-(OK1-VB)") (class "Default")
      (node (ref "OK1") (pin "7") (pinfunction "VB_7") (pintype "passive"))
      (node (ref "R8") (pin "2") (pinfunction "2_2") (pintype "passive"))
    )
    (net (code "44") (name "Net-(Q1-PadB)") (class "Default")
      (node (ref "Q1") (pin "B") (pinfunction "B_B") (pintype "passive"))
      (node (ref "R1") (pin "2") (pinfunction "2_2") (pintype "passive"))
    )
    (net (code "45") (name "Net-(Q1-PadC)") (class "Default")
      (node (ref "Q1") (pin "C") (pinfunction "C_C") (pintype "passive"))
      (node (ref "R2") (pin "1") (pinfunction "1_1") (pintype "passive"))
      (node (ref "R3") (pin "1") (pinfunction "1_1") (pintype "passive"))
    )
    (net (code "46") (name "Net-(Q2-PadB)") (class "Default")
      (node (ref "Q2") (pin "B") (pinfunction "B_B") (pintype "passive"))
      (node (ref "R2") (pin "2") (pinfunction "2_2") (pintype "passive"))
    )
    (net (code "47") (name "Net-(Q2-PadC)") (class "Default")
      (node (ref "Q2") (pin "C") (pinfunction "C_C") (pintype "passive"))
      (node (ref "R4") (pin "1") (pinfunction "1_1") (pintype "passive"))
      (node (ref "R5") (pin "1") (pinfunction "1_1") (pintype "passive"))
    )
    (net (code "48") (name "Net-(R32-Pad1)") (class "Default")
      (node (ref "R32") (pin "1") (pinfunction "1_1") (pintype "passive"))
      (node (ref "SV6") (pin "1") (pinfunction "1_1") (pintype "passive"))
    )
    (net (code "49") (name "Net-(R33-Pad1)") (class "Default")
      (node (ref "R33") (pin "1") (pinfunction "1_1") (pintype "passive"))
      (node (ref "SV6") (pin "3") (pinfunction "3_3") (pintype "passive"))
    )
    (net (code "50") (name "Net-(R34-Pad1)") (class "Default")
      (node (ref "R34") (pin "1") (pinfunction "1_1") (pintype "passive"))
      (node (ref "SV6") (pin "5") (pinfunction "5_5") (pintype "passive"))
    )
    (net (code "51") (name "Net-(U1A-XTALOUT)") (class "Default")
      (node (ref "C7") (pin "1") (pinfunction "1_1") (pintype "passive"))
      (node (ref "U1") (pin "7") (pinfunction "XTALOUT_7") (pintype "output"))
      (node (ref "Y1") (pin "1") (pinfunction "1_1") (pintype "passive"))
    )
    (net (code "52") (name "Net-(U2-C+)") (class "Default")
      (node (ref "C1") (pin "2") (pinfunction "2_2") (pintype "passive"))
      (node (ref "U2") (pin "6") (pinfunction "C+_6") (pintype "passive"))
    )
    (net (code "53") (name "Net-(U2-C-)") (class "Default")
      (node (ref "C1") (pin "1") (pinfunction "1_1") (pintype "passive"))
      (node (ref "U2") (pin "5") (pinfunction "C-_5") (pintype "passive"))
    )
    (net (code "54") (name "Net-(U2-FB)") (class "Default")
      (node (ref "R11") (pin "1") (pinfunction "1_1") (pintype "passive"))
      (node (ref "R12") (pin "2") (pinfunction "2_2") (pintype "passive"))
      (node (ref "U2") (pin "8") (pinfunction "FB_8") (pintype "input"))
    )
    (net (code "55") (name "Net-(U2-VIN)") (class "Default")
      (node (ref "C3") (pin "1") (pinfunction "1_1") (pintype "passive"))
      (node (ref "D2") (pin "C") (pinfunction "C_C") (pintype "passive"))
      (node (ref "U2") (pin "3") (pinfunction "VIN_3") (pintype "power_in"))
      (node (ref "U2") (pin "7") (pinfunction "~{SHDN}_7") (pintype "input"))
    )
    (net (code "56") (name "POK_3V3") (class "Default")
      (node (ref "R31") (pin "1") (pinfunction "1_1") (pintype "passive"))
      (node (ref "U1") (pin "1") (pinfunction "PIO2_6_1") (pintype "bidirectional"))
      (node (ref "U2") (pin "1") (pinfunction "PGOOD_1") (pintype "output"))
    )
    (net (code "57") (name "P_VOL") (class "Default")
      (node (ref "SV5") (pin "3") (pinfunction "3_3") (pintype "passive"))
      (node (ref "U1") (pin "34") (pinfunction "R/PIO1_1/AD2/CT32B1_MAT0_34") (pintype "bidirectional"))
    )
    (net (code "58") (name "RX_C_2") (class "Default")
      (node (ref "C13") (pin "1") (pinfunction "1_1") (pintype "passive"))
      (node (ref "SV2") (pin "2") (pinfunction "2_2") (pintype "passive"))
      (node (ref "X6") (pin "2") (pinfunction "2_2") (pintype "passive"))
    )
    (net (code "59") (name "RX_C_4") (class "Default")
      (node (ref "FB3") (pin "1") (pinfunction "1_1") (pintype "passive"))
      (node (ref "SV2") (pin "4") (pinfunction "4_4") (pintype "passive"))
      (node (ref "X6") (pin "4") (pinfunction "4_4") (pintype "passive"))
    )
    (net (code "60") (name "RX_C_5") (class "Default")
      (node (ref "FB4") (pin "1") (pinfunction "1_1") (pintype "passive"))
      (node (ref "SV2") (pin "5") (pinfunction "5_5") (pintype "passive"))
      (node (ref "X6") (pin "5") (pinfunction "5_5") (pintype "passive"))
    )
    (net (code "61") (name "RX_C_S") (class "Default")
      (node (ref "C14") (pin "1") (pinfunction "1_1") (pintype "passive"))
      (node (ref "SV2") (pin "6") (pinfunction "6_6") (pintype "passive"))
      (node (ref "X6") (pin "PE") (pinfunction "PE_PE") (pintype "power_in"))
      (node (ref "X6") (pin "PE@") (pinfunction "PE_PE@") (pintype "power_in"))
    )
    (net (code "62") (name "RX_L") (class "Default")
      (node (ref "OK1") (pin "6") (pinfunction "VO_6") (pintype "passive"))
      (node (ref "R9") (pin "1") (pinfunction "1_1") (pintype "passive"))
      (node (ref "U1") (pin "46") (pinfunction "PIO1_6/RXD/CT32B0_MAT0_46") (pintype "bidirectional"))
    )
    (net (code "63") (name "SCL") (class "Default")
      (node (ref "R36") (pin "1") (pinfunction "1_1") (pintype "passive"))
      (node (ref "SV7") (pin "4") (pinfunction "4_4") (pintype "passive"))
      (node (ref "U1") (pin "15") (pinfunction "PIO0_4_15") (pintype "bidirectional"))
    )
    (net (code "64") (name "SDA") (class "Default")
      (node (ref "R35") (pin "1") (pinfunction "1_1") (pintype "passive"))
      (node (ref "SV7") (pin "2") (pinfunction "2_2") (pintype "passive"))
      (node (ref "U1") (pin "16") (pinfunction "PIO0_5_16") (pintype "bidirectional"))
    )
    (net (code "65") (name "TX_C_4") (class "Default")
      (node (ref "FB2") (pin "2") (pinfunction "2_2") (pintype "passive"))
      (node (ref "SV1") (pin "4") (pinfunction "4_4") (pintype "passive"))
      (node (ref "X5") (pin "4") (pinfunction "4_4") (pintype "passive"))
    )
    (net (code "66") (name "TX_C_5") (class "Default")
      (node (ref "FB1") (pin "2") (pinfunction "2_2") (pintype "passive"))
      (node (ref "SV1") (pin "5") (pinfunction "5_5") (pintype "passive"))
      (node (ref "X5") (pin "5") (pinfunction "5_5") (pintype "passive"))
    )
    (net (code "67") (name "TX_L") (class "Default")
      (node (ref "R1") (pin "1") (pinfunction "1_1") (pintype "passive"))
      (node (ref "U1") (pin "47") (pinfunction "PIO1_7/TXD/CT32B0_MAT1_47") (pintype "bidirectional"))
    )
    (net (code "68") (name "XTALIN") (class "Default")
      (node (ref "C8") (pin "1") (pinfunction "1_1") (pintype "passive"))
      (node (ref "SJ2") (pin "2") (pinfunction "2_2") (pintype "passive"))
      (node (ref "U1") (pin "6") (pinfunction "XTALIN_6") (pintype "input"))
      (node (ref "Y1") (pin "2") (pinfunction "2_2") (pintype "passive"))
    )
    (net (code "69") (name "unconnected-(J1-Pad7)") (class "Default")
      (node (ref "J1") (pin "7") (pinfunction "7_7") (pintype "passive"))
    )
    (net (code "70") (name "unconnected-(J1-Pad8)") (class "Default")
      (node (ref "J1") (pin "8") (pinfunction "8_8") (pintype "passive"))
    )
    (net (code "71") (name "unconnected-(SV1-Pad1)") (class "Default")
      (node (ref "SV1") (pin "1") (pinfunction "1_1") (pintype "passive"))
    )
    (net (code "72") (name "unconnected-(SV1-Pad3)") (class "Default")
      (node (ref "SV1") (pin "3") (pinfunction "3_3") (pintype "passive"))
    )
    (net (code "73") (name "unconnected-(SV2-Pad1)") (class "Default")
      (node (ref "SV2") (pin "1") (pinfunction "1_1") (pintype "passive"))
    )
    (net (code "74") (name "unconnected-(SV2-Pad3)") (class "Default")
      (node (ref "SV2") (pin "3") (pinfunction "3_3") (pintype "passive"))
    )
    (net (code "75") (name "unconnected-(SV5-Pad2)") (class "Default")
      (node (ref "SV5") (pin "2") (pinfunction "2_2") (pintype "passive"))
    )
    (net (code "76") (name "unconnected-(SV5-Pad4)") (class "Default")
      (node (ref "SV5") (pin "4") (pinfunction "4_4") (pintype "passive"))
    )
    (net (code "77") (name "unconnected-(SV5-Pad6)") (class "Default")
      (node (ref "SV5") (pin "6") (pinfunction "6_6") (pintype "passive"))
    )
    (net (code "78") (name "unconnected-(U1A-PIO2_0{slash}~{DTR}{slash}SSEL1-Pad2)") (class "Default")
      (node (ref "U1") (pin "2") (pinfunction "PIO2_0/~{DTR}/SSEL1_2") (pintype "bidirectional"))
    )
    (net (code "79") (name "unconnected-(U1B-PIO1_5{slash}~{RTS}{slash}CT32B0_CAP0-Pad45)") (class "Default")
      (node (ref "U1") (pin "45") (pinfunction "PIO1_5/~{RTS}/CT32B0_CAP0_45") (pintype "bidirectional"))
    )
    (net (code "80") (name "unconnected-(U1B-PIO1_11{slash}AD7-Pad42)") (class "Default")
      (node (ref "U1") (pin "42") (pinfunction "PIO1_11/AD7_42") (pintype "bidirectional"))
    )
    (net (code "81") (name "unconnected-(U1B-PIO3_2{slash}~{DCD}-Pad43)") (class "Default")
      (node (ref "U1") (pin "43") (pinfunction "PIO3_2/~{DCD}_43") (pintype "bidirectional"))
    )
    (net (code "82") (name "unconnected-(U1B-PIO3_3{slash}~{RI}-Pad48)") (class "Default")
      (node (ref "U1") (pin "48") (pinfunction "PIO3_3/~{RI}_48") (pintype "bidirectional"))
    )
    (net (code "83") (name "unconnected-(X5-Pad1)") (class "Default")
      (node (ref "X5") (pin "1") (pinfunction "1_1") (pintype "passive"))
    )
    (net (code "84") (name "unconnected-(X5-Pad3)") (class "Default")
      (node (ref "X5") (pin "3") (pinfunction "3_3") (pintype "passive"))
    )
    (net (code "85") (name "unconnected-(X6-Pad1)") (class "Default")
      (node (ref "X6") (pin "1") (pinfunction "1_1") (pintype "passive"))
    )
    (net (code "86") (name "unconnected-(X6-Pad3)") (class "Default")
      (node (ref "X6") (pin "3") (pinfunction "3_3") (pintype "passive"))
    )
  )
)
